# Audio.net
KiCad netlist of a schematic drawn in Altium Designer
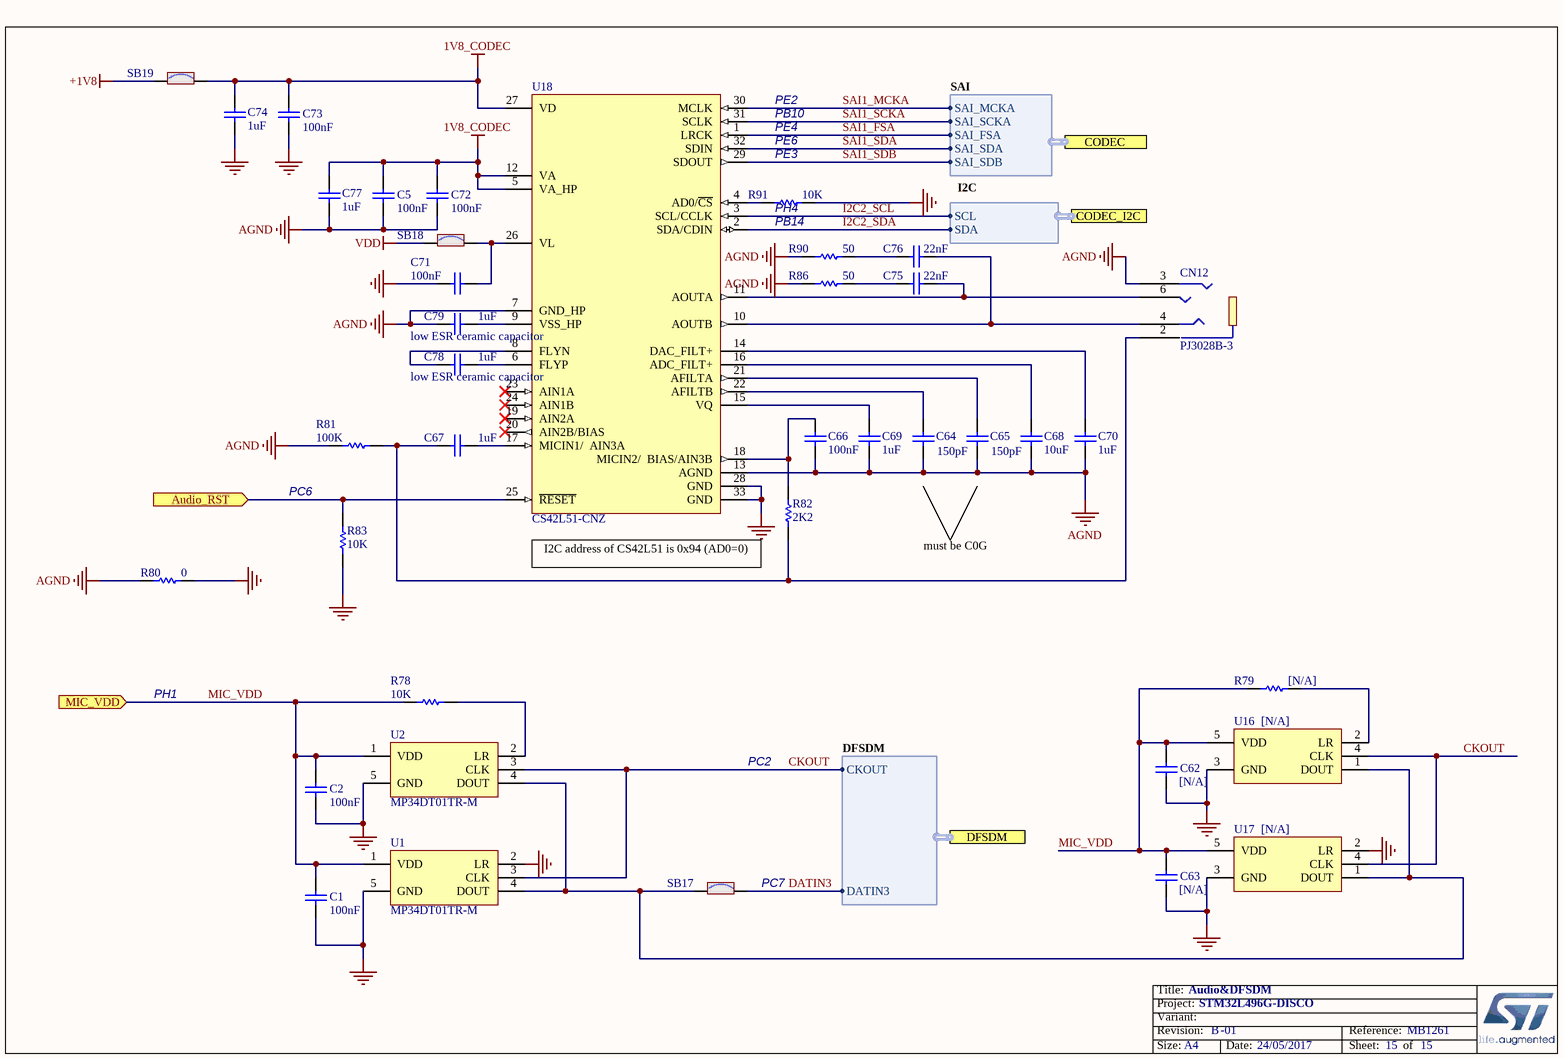
[diagram p0: Audio.SchDoc]

(export (version "E")
  (design (tool "Eeschema 10.0.6"))
  (components
    (comp (ref "C1")
      (value "100nF")
      (footprint "0603C")
      (description "Capacitor,100nF,10%,16V,X7R,0603,YAGEO")
      (fields (field (name "Comment") "CC0603KRX7R7BB104") (field (name "PUBLISHER") "Altium Limited"))
      (libsource (lib "Miscellaneous Devices") (part "Cap"))
    )
    (comp (ref "C2")
      (value "100nF")
      (footprint "0603C")
      (description "Capacitor,100nF,10%,16V,X7R,0603,YAGEO")
      (fields (field (name "Comment") "CC0603KRX7R7BB104") (field (name "PUBLISHER") "Altium Limited"))
      (libsource (lib "Miscellaneous Devices") (part "Cap"))
    )
    (comp (ref "C5")
      (value "100nF")
      (footprint "0603C")
      (description "Capacitor,100nF,10%,16V,X7R,0603,YAGEO")
      (fields (field (name "Comment") "CC0603KRX7R7BB104") (field (name "PUBLISHER") "Altium Limited"))
      (libsource (lib "Miscellaneous Devices") (part "Cap"))
    )
    (comp (ref "C62")
      (value "[N/A]")
      (footprint "0603C")
      (description "Capacitor,100nF,10%,16V,X7R,0603,YAGEO")
      (fields (field (name "PUBLISHER") "Altium Limited"))
      (libsource (lib "Miscellaneous Devices") (part "Cap"))
    )
    (comp (ref "C63")
      (value "[N/A]")
      (footprint "0603C")
      (description "Capacitor,100nF,10%,16V,X7R,0603,YAGEO")
      (fields (field (name "PUBLISHER") "Altium Limited"))
      (libsource (lib "Miscellaneous Devices") (part "Cap"))
    )
    (comp (ref "C64")
      (value "150pF")
      (footprint "0603C")
      (description "Capacitor,150pF,0603,50V,5%,NPO")
      (fields (field (name "Comment") "CC0603JRNPO9BN151") (field (name "PUBLISHER") "Altium Limited"))
      (libsource (lib "Miscellaneous Devices") (part "Cap"))
    )
    (comp (ref "C65")
      (value "150pF")
      (footprint "0603C")
      (description "Capacitor,150pF,0603,50V,5%,NPO")
      (fields (field (name "Comment") "CC0603JRNPO9BN151") (field (name "PUBLISHER") "Altium Limited"))
      (libsource (lib "Miscellaneous Devices") (part "Cap"))
    )
    (comp (ref "C66")
      (value "100nF")
      (footprint "0603C")
      (description "Capacitor,100nF,10%,16V,X7R,0603,YAGEO")
      (fields (field (name "Comment") "CC0603KRX7R7BB104") (field (name "PUBLISHER") "Altium Limited"))
      (libsource (lib "Miscellaneous Devices") (part "Cap"))
    )
    (comp (ref "C67")
      (value "1uF")
      (footprint "0603C")
      (description "Capacitor,1uF,0603,16V,10%,X5R,YAGEO")
      (fields (field (name "Comment") "CC0603KRX5R7BB105") (field (name "PUBLISHER") "Altium Limited"))
      (libsource (lib "Miscellaneous Devices") (part "Cap"))
    )
    (comp (ref "C68")
      (value "10uF")
      (footprint "0603C")
      (description "Capacitor,10uF,10%,10V,X5R,0603,C1608X5R1A106KT000E")
      (fields (field (name "Comment") "C1608X5R1A106KT000E") (field (name "PUBLISHER") "Altium Limited"))
      (libsource (lib "Miscellaneous Devices") (part "Cap"))
    )
    (comp (ref "C69")
      (value "1uF")
      (footprint "0603C")
      (description "Capacitor,1uF,0603,16V,10%,X5R,YAGEO")
      (fields (field (name "Comment") "CC0603KRX5R7BB105") (field (name "PUBLISHER") "Altium Limited"))
      (libsource (lib "Miscellaneous Devices") (part "Cap"))
    )
    (comp (ref "C70")
      (value "1uF")
      (footprint "0603C")
      (description "Capacitor,1uF,0603,16V,10%,X5R,YAGEO")
      (fields (field (name "Comment") "CC0603KRX5R7BB105") (field (name "PUBLISHER") "Altium Limited"))
      (libsource (lib "Miscellaneous Devices") (part "Cap"))
    )
    (comp (ref "C71")
      (value "100nF")
      (footprint "0603C")
      (description "Capacitor,100nF,10%,16V,X7R,0603,YAGEO")
      (fields (field (name "Comment") "CC0603KRX7R7BB104") (field (name "PUBLISHER") "Altium Limited"))
      (libsource (lib "Miscellaneous Devices") (part "Cap"))
    )
    (comp (ref "C72")
      (value "100nF")
      (footprint "0603C")
      (description "Capacitor,100nF,10%,16V,X7R,0603,YAGEO")
      (fields (field (name "Comment") "CC0603KRX7R7BB104") (field (name "PUBLISHER") "Altium Limited"))
      (libsource (lib "Miscellaneous Devices") (part "Cap"))
    )
    (comp (ref "C73")
      (value "100nF")
      (footprint "0603C")
      (description "Capacitor,100nF,10%,16V,X7R,0603,YAGEO")
      (fields (field (name "Comment") "CC0603KRX7R7BB104") (field (name "PUBLISHER") "Altium Limited"))
      (libsource (lib "Miscellaneous Devices") (part "Cap"))
    )
    (comp (ref "C74")
      (value "1uF")
      (footprint "0603C")
      (description "Capacitor,1uF,0603,16V,10%,X5R,YAGEO")
      (fields (field (name "Comment") "CC0603KRX5R7BB105") (field (name "PUBLISHER") "Altium Limited"))
      (libsource (lib "Miscellaneous Devices") (part "Cap"))
    )
    (comp (ref "C75")
      (value "22nF")
      (footprint "0603C")
      (description "Capacitor,22nF,10%,25V,X7R,0603")
      (fields (field (name "Comment") "CC0603KRX7R8BB223") (field (name "PUBLISHER") "Altium Limited"))
      (libsource (lib "Miscellaneous Devices") (part "Cap"))
    )
    (comp (ref "C76")
      (value "22nF")
      (footprint "0603C")
      (description "Capacitor,22nF,10%,25V,X7R,0603")
      (fields (field (name "Comment") "CC0603KRX7R8BB223") (field (name "PUBLISHER") "Altium Limited"))
      (libsource (lib "Miscellaneous Devices") (part "Cap"))
    )
    (comp (ref "C77")
      (value "1uF")
      (footprint "0603C")
      (description "Capacitor,1uF,0603,16V,10%,X5R,YAGEO")
      (fields (field (name "Comment") "CC0603KRX5R7BB105") (field (name "PUBLISHER") "Altium Limited"))
      (libsource (lib "Miscellaneous Devices") (part "Cap"))
    )
    (comp (ref "C78")
      (value "1uF")
      (footprint "0603C")
      (description "Capacitor,1uF,0603,16V,10%,X5R,YAGEO")
      (fields (field (name "Comment") "CC0603KRX5R7BB105") (field (name "PUBLISHER") "Altium Limited"))
      (libsource (lib "Miscellaneous Devices") (part "Cap"))
    )
    (comp (ref "C79")
      (value "1uF")
      (footprint "0603C")
      (description "Capacitor,1uF,0603,16V,10%,X5R,YAGEO")
      (fields (field (name "Comment") "CC0603KRX5R7BB105") (field (name "PUBLISHER") "Altium Limited"))
      (libsource (lib "Miscellaneous Devices") (part "Cap"))
    )
    (comp (ref "CN12") (value "PJ3028B-3") (footprint "PJ3028B") (libsource (lib "MB786") (part "PJ3028B-3")))
    (comp (ref "R78")
      (value "10K")
      (footprint "0603R")
      (description "Resistor,10K,0603,1%,YAGEO")
      (fields (field (name "Comment") "RC0603FR-0710KL") (field (name "PUBLISHER") "Altium Limited"))
      (libsource (lib "Miscellaneous Devices") (part "res1"))
    )
    (comp (ref "R79")
      (value "[N/A]")
      (footprint "0603R")
      (description "Resistor,10K,0603,1%,YAGEO")
      (fields (field (name "PUBLISHER") "Altium Limited"))
      (libsource (lib "Miscellaneous Devices") (part "res1"))
    )
    (comp (ref "R80")
      (value "0")
      (footprint "0603R")
      (description "Resistor, 0 ,0603,1%,YAGEO")
      (fields (field (name "Comment") "RC0603JR-070RL") (field (name "PUBLISHER") "Altium Limited"))
      (libsource (lib "Miscellaneous Devices") (part "res1"))
    )
    (comp (ref "R81")
      (value "100K")
      (footprint "0603R")
      (description "Resistor,100K,0603,1%,YAGEO")
      (fields (field (name "Comment") "RC0603FR-07100KL") (field (name "PUBLISHER") "Altium Limited"))
      (libsource (lib "Miscellaneous Devices") (part "res1"))
    )
    (comp (ref "R82")
      (value "2K2")
      (footprint "0603R")
      (description "Resistor,2.2K,0603,1%,YAGEO")
      (fields (field (name "Comment") "RC0603FR-072K2L") (field (name "PUBLISHER") "Altium Limited"))
      (libsource (lib "Miscellaneous Devices") (part "res1"))
    )
    (comp (ref "R83")
      (value "10K")
      (footprint "0603R")
      (description "Resistor,10K,0603,1%,YAGEO")
      (fields (field (name "Comment") "RC0603FR-0710KL") (field (name "PUBLISHER") "Altium Limited"))
      (libsource (lib "Miscellaneous Devices") (part "res1"))
    )
    (comp (ref "R86")
      (value "50")
      (footprint "0603R")
      (description "Resistor,50R,0603,1%,YAGEO")
      (fields (field (name "Comment") "RC0603FR-0750RL") (field (name "PUBLISHER") "Altium Limited"))
      (libsource (lib "Miscellaneous Devices") (part "res1"))
    )
    (comp (ref "R90")
      (value "50")
      (footprint "0603R")
      (description "Resistor,50R,0603,1%,YAGEO")
      (fields (field (name "Comment") "RC0603FR-0750RL") (field (name "PUBLISHER") "Altium Limited"))
      (libsource (lib "Miscellaneous Devices") (part "res1"))
    )
    (comp (ref "R91")
      (value "10K")
      (footprint "0603R")
      (description "Resistor,10K,0603,1%,YAGEO")
      (fields (field (name "Comment") "RC0603FR-0710KL") (field (name "PUBLISHER") "Altium Limited"))
      (libsource (lib "Miscellaneous Devices") (part "res1"))
    )
    (comp (ref "SB17")
      (value "Solder Bridge ON")
      (footprint "SB_0603")
      (libsource (lib "MCD_TOOLS") (part "SB_ON"))
    )
    (comp (ref "SB18")
      (value "Solder Bridge ON")
      (footprint "SB_0603")
      (libsource (lib "MCD_TOOLS") (part "SB_ON"))
    )
    (comp (ref "SB19")
      (value "Solder Bridge ON")
      (footprint "SB_0603")
      (libsource (lib "MCD_TOOLS") (part "SB_ON"))
    )
    (comp (ref "U1")
      (value "MP34DT01TR-M")
      (footprint "MP34DT01TR")
      (description "MEMS audio sensor")
      (fields (field (name "PUBLISHER") "Altium Limited"))
      (libsource (lib "mb1045") (part "MP34DT01TR"))
    )
    (comp (ref "U2")
      (value "MP34DT01TR-M")
      (footprint "MP34DT01TR")
      (description "MEMS audio sensor")
      (fields (field (name "PUBLISHER") "Altium Limited"))
      (libsource (lib "mb1045") (part "MP34DT01TR"))
    )
    (comp (ref "U16")
      (value "[N/A]")
      (footprint "RHLGA5LD")
      (description "MEMS micro")
      (fields (field (name "PUBLISHER") "STM"))
      (libsource (lib "Big Orga") (part "MP23DB01MM"))
    )
    (comp (ref "U17")
      (value "[N/A]")
      (footprint "RHLGA5LD")
      (description "MEMS micro")
      (fields (field (name "PUBLISHER") "STM"))
      (libsource (lib "Big Orga") (part "MP23DB01MM"))
    )
    (comp (ref "U18")
      (value "CS42L51-CNZ")
      (footprint "QFN32_0R5_5X5")
      (description "Low-Power, Stereo Codec with Headphone Amp")
      (libsource (lib "Big Orga") (part "CS42L51-CNZ"))
    )
  )
  (nets
    (net (code "4") (name "+1V8") (class "Default")
      (node (ref "SB19") (pin "1") (pinfunction "1_1") (pintype "passive"))
    )
    (net (code "5") (name "/Audio_RST") (class "Default")
      (node (ref "R83") (pin "2") (pinfunction "2_2") (pintype "passive"))
      (node (ref "U18") (pin "25") (pinfunction "~{RESET}_25") (pintype "input"))
    )
    (net (code "6") (name "/CKOUT") (class "Default")
      (node (ref "U1") (pin "3") (pinfunction "CLK_3") (pintype "passive"))
      (node (ref "U16") (pin "4") (pinfunction "CLK_4") (pintype "passive"))
      (node (ref "U17") (pin "4") (pinfunction "CLK_4") (pintype "passive"))
      (node (ref "U2") (pin "3") (pinfunction "CLK_3") (pintype "passive"))
    )
    (net (code "7") (name "/DATIN3") (class "Default")
      (node (ref "SB17") (pin "2") (pinfunction "2_2") (pintype "passive"))
    )
    (net (code "8") (name "/I2C2_SCL") (class "Default")
      (node (ref "U18") (pin "3") (pinfunction "SCL/CCLK_3") (pintype "input"))
    )
    (net (code "9") (name "/I2C2_SDA") (class "Default")
      (node (ref "U18") (pin "2") (pinfunction "SDA/CDIN_2") (pintype "bidirectional"))
    )
    (net (code "10") (name "/MIC_VDD") (class "Default")
      (node (ref "C1") (pin "1") (pinfunction "1_1") (pintype "passive"))
      (node (ref "C2") (pin "1") (pinfunction "1_1") (pintype "passive"))
      (node (ref "C62") (pin "1") (pinfunction "1_1") (pintype "passive"))
      (node (ref "C63") (pin "1") (pinfunction "1_1") (pintype "passive"))
      (node (ref "R78") (pin "2") (pinfunction "2_2") (pintype "passive"))
      (node (ref "R79") (pin "2") (pinfunction "2_2") (pintype "passive"))
      (node (ref "U1") (pin "1") (pinfunction "VDD_1") (pintype "passive"))
      (node (ref "U16") (pin "5") (pinfunction "VDD_5") (pintype "passive"))
      (node (ref "U17") (pin "5") (pinfunction "VDD_5") (pintype "passive"))
      (node (ref "U2") (pin "1") (pinfunction "VDD_1") (pintype "passive"))
    )
    (net (code "11") (name "/SAI1_FSA") (class "Default")
      (node (ref "U18") (pin "1") (pinfunction "LRCK_1") (pintype "input"))
    )
    (net (code "12") (name "/SAI1_MCKA") (class "Default")
      (node (ref "U18") (pin "30") (pinfunction "MCLK_30") (pintype "input"))
    )
    (net (code "13") (name "/SAI1_SCKA") (class "Default")
      (node (ref "U18") (pin "31") (pinfunction "SCLK_31") (pintype "input"))
    )
    (net (code "14") (name "/SAI1_SDA") (class "Default")
      (node (ref "U18") (pin "32") (pinfunction "SDIN_32") (pintype "input"))
    )
    (net (code "15") (name "/SAI1_SDB") (class "Default")
      (node (ref "U18") (pin "29") (pinfunction "SDOUT_29") (pintype "output"))
    )
    (net (code "19") (name "1V8_CODEC") (class "Default")
      (node (ref "C5") (pin "1") (pinfunction "1_1") (pintype "passive"))
      (node (ref "C72") (pin "1") (pinfunction "1_1") (pintype "passive"))
      (node (ref "C73") (pin "1") (pinfunction "1_1") (pintype "passive"))
      (node (ref "C74") (pin "1") (pinfunction "1_1") (pintype "passive"))
      (node (ref "C77") (pin "1") (pinfunction "1_1") (pintype "passive"))
      (node (ref "SB19") (pin "2") (pinfunction "2_2") (pintype "passive"))
      (node (ref "U18") (pin "12") (pinfunction "VA_12") (pintype "power_in"))
      (node (ref "U18") (pin "27") (pinfunction "VD_27") (pintype "power_in"))
      (node (ref "U18") (pin "5") (pinfunction "VA_HP_5") (pintype "power_in"))
    )
    (net (code "20") (name "AGND") (class "Default")
      (node (ref "C5") (pin "2") (pinfunction "2_2") (pintype "passive"))
      (node (ref "C64") (pin "2") (pinfunction "2_2") (pintype "passive"))
      (node (ref "C65") (pin "2") (pinfunction "2_2") (pintype "passive"))
      (node (ref "C66") (pin "1") (pinfunction "1_1") (pintype "passive"))
      (node (ref "C68") (pin "1") (pinfunction "1_1") (pintype "passive"))
      (node (ref "C69") (pin "1") (pinfunction "1_1") (pintype "passive"))
      (node (ref "C70") (pin "1") (pinfunction "1_1") (pintype "passive"))
      (node (ref "C72") (pin "2") (pinfunction "2_2") (pintype "passive"))
      (node (ref "C77") (pin "2") (pinfunction "2_2") (pintype "passive"))
      (node (ref "C79") (pin "1") (pinfunction "1_1") (pintype "passive"))
      (node (ref "CN12") (pin "3") (pintype "passive"))
      (node (ref "R80") (pin "2") (pinfunction "2_2") (pintype "passive"))
      (node (ref "R81") (pin "2") (pinfunction "2_2") (pintype "passive"))
      (node (ref "R86") (pin "2") (pinfunction "2_2") (pintype "passive"))
      (node (ref "R90") (pin "2") (pinfunction "2_2") (pintype "passive"))
      (node (ref "U18") (pin "13") (pinfunction "AGND_13") (pintype "power_in"))
      (node (ref "U18") (pin "7") (pinfunction "GND_HP_7") (pintype "power_in"))
    )
    (net (code "21") (name "GND") (class "Default")
      (node (ref "C1") (pin "2") (pinfunction "2_2") (pintype "passive"))
      (node (ref "C2") (pin "2") (pinfunction "2_2") (pintype "passive"))
      (node (ref "C62") (pin "2") (pinfunction "2_2") (pintype "passive"))
      (node (ref "C63") (pin "2") (pinfunction "2_2") (pintype "passive"))
      (node (ref "C71") (pin "1") (pinfunction "1_1") (pintype "passive"))
      (node (ref "C73") (pin "2") (pinfunction "2_2") (pintype "passive"))
      (node (ref "C74") (pin "2") (pinfunction "2_2") (pintype "passive"))
      (node (ref "R80") (pin "1") (pinfunction "1_1") (pintype "passive"))
      (node (ref "R83") (pin "1") (pinfunction "1_1") (pintype "passive"))
      (node (ref "R91") (pin "1") (pinfunction "1_1") (pintype "passive"))
      (node (ref "U1") (pin "2") (pinfunction "LR_2") (pintype "passive"))
      (node (ref "U1") (pin "5") (pinfunction "GND_5") (pintype "passive"))
      (node (ref "U16") (pin "3") (pinfunction "GND_3") (pintype "passive"))
      (node (ref "U17") (pin "2") (pinfunction "LR_2") (pintype "passive"))
      (node (ref "U17") (pin "3") (pinfunction "GND_3") (pintype "passive"))
      (node (ref "U18") (pin "28") (pinfunction "GND_28") (pintype "power_in"))
      (node (ref "U18") (pin "33") (pinfunction "GND_33") (pintype "power_in"))
      (node (ref "U2") (pin "5") (pinfunction "GND_5") (pintype "passive"))
    )
    (net (code "22") (name "Net-(C67-Pad1)") (class "Default")
      (node (ref "C67") (pin "1") (pinfunction "1_1") (pintype "passive"))
      (node (ref "CN12") (pin "2") (pintype "passive"))
      (node (ref "R81") (pin "1") (pinfunction "1_1") (pintype "passive"))
      (node (ref "R82") (pin "1") (pinfunction "1_1") (pintype "passive"))
    )
    (net (code "23") (name "Net-(C75-Pad2)") (class "Default")
      (node (ref "C75") (pin "2") (pinfunction "2_2") (pintype "passive"))
      (node (ref "R86") (pin "1") (pinfunction "1_1") (pintype "passive"))
    )
    (net (code "24") (name "Net-(C76-Pad2)") (class "Default")
      (node (ref "C76") (pin "2") (pinfunction "2_2") (pintype "passive"))
      (node (ref "R90") (pin "1") (pinfunction "1_1") (pintype "passive"))
    )
    (net (code "25") (name "Net-(U1-DOUT)") (class "Default")
      (node (ref "SB17") (pin "1") (pinfunction "1_1") (pintype "passive"))
      (node (ref "U1") (pin "4") (pinfunction "DOUT_4") (pintype "passive"))
      (node (ref "U16") (pin "1") (pinfunction "DOUT_1") (pintype "passive"))
      (node (ref "U17") (pin "1") (pinfunction "DOUT_1") (pintype "passive"))
      (node (ref "U2") (pin "4") (pinfunction "DOUT_4") (pintype "passive"))
    )
    (net (code "26") (name "Net-(U2-LR)") (class "Default")
      (node (ref "R78") (pin "1") (pinfunction "1_1") (pintype "passive"))
      (node (ref "U2") (pin "2") (pinfunction "LR_2") (pintype "passive"))
    )
    (net (code "27") (name "Net-(U16-LR)") (class "Default")
      (node (ref "R79") (pin "1") (pinfunction "1_1") (pintype "passive"))
      (node (ref "U16") (pin "2") (pinfunction "LR_2") (pintype "passive"))
    )
    (net (code "28") (name "Net-(U18-AD0{slash}~{CS})") (class "Default")
      (node (ref "R91") (pin "2") (pinfunction "2_2") (pintype "passive"))
      (node (ref "U18") (pin "4") (pinfunction "AD0/~{CS}_4") (pintype "input"))
    )
    (net (code "29") (name "Net-(U18-ADC_FILT+)") (class "Default")
      (node (ref "C68") (pin "2") (pinfunction "2_2") (pintype "passive"))
      (node (ref "U18") (pin "16") (pinfunction "ADC_FILT+_16") (pintype "power_in"))
    )
    (net (code "30") (name "Net-(U18-AFILTA)") (class "Default")
      (node (ref "C65") (pin "1") (pinfunction "1_1") (pintype "passive"))
      (node (ref "U18") (pin "21") (pinfunction "AFILTA_21") (pintype "output"))
    )
    (net (code "31") (name "Net-(U18-AFILTB)") (class "Default")
      (node (ref "C64") (pin "1") (pinfunction "1_1") (pintype "passive"))
      (node (ref "U18") (pin "22") (pinfunction "AFILTB_22") (pintype "output"))
    )
    (net (code "32") (name "Net-(U18-AOUTA)") (class "Default")
      (node (ref "C75") (pin "1") (pinfunction "1_1") (pintype "passive"))
      (node (ref "CN12") (pin "6") (pintype "passive"))
      (node (ref "U18") (pin "11") (pinfunction "AOUTA_11") (pintype "output"))
    )
    (net (code "33") (name "Net-(U18-AOUTB)") (class "Default")
      (node (ref "C76") (pin "1") (pinfunction "1_1") (pintype "passive"))
      (node (ref "CN12") (pin "4") (pintype "passive"))
      (node (ref "U18") (pin "10") (pinfunction "AOUTB_10") (pintype "output"))
    )
    (net (code "34") (name "Net-(U18-DAC_FILT+)") (class "Default")
      (node (ref "C70") (pin "2") (pinfunction "2_2") (pintype "passive"))
      (node (ref "U18") (pin "14") (pinfunction "DAC_FILT+_14") (pintype "power_in"))
    )
    (net (code "35") (name "Net-(U18-FLYN)") (class "Default")
      (node (ref "C78") (pin "1") (pinfunction "1_1") (pintype "passive"))
      (node (ref "U18") (pin "8") (pinfunction "FLYN_8") (pintype "passive"))
    )
    (net (code "36") (name "Net-(U18-FLYP)") (class "Default")
      (node (ref "C78") (pin "2") (pinfunction "2_2") (pintype "passive"))
      (node (ref "U18") (pin "6") (pinfunction "FLYP_6") (pintype "passive"))
    )
    (net (code "37") (name "Net-(U18-MICIN1{slash}__AIN3A)") (class "Default")
      (node (ref "C67") (pin "2") (pinfunction "2_2") (pintype "passive"))
      (node (ref "U18") (pin "17") (pinfunction "MICIN1/__AIN3A_17") (pintype "input"))
    )
    (net (code "38") (name "Net-(U18-MICIN2{slash}__BIAS{slash}AIN3B)") (class "Default")
      (node (ref "C66") (pin "2") (pinfunction "2_2") (pintype "passive"))
      (node (ref "R82") (pin "2") (pinfunction "2_2") (pintype "passive"))
      (node (ref "U18") (pin "18") (pinfunction "MICIN2/__BIAS/AIN3B_18") (pintype "output"))
    )
    (net (code "39") (name "Net-(U18-VL)") (class "Default")
      (node (ref "C71") (pin "2") (pinfunction "2_2") (pintype "passive"))
      (node (ref "SB18") (pin "2") (pinfunction "2_2") (pintype "passive"))
      (node (ref "U18") (pin "26") (pinfunction "VL_26") (pintype "power_in"))
    )
    (net (code "40") (name "Net-(U18-VQ)") (class "Default")
      (node (ref "C69") (pin "2") (pinfunction "2_2") (pintype "passive"))
      (node (ref "U18") (pin "15") (pinfunction "VQ_15") (pintype "power_in"))
    )
    (net (code "41") (name "Net-(U18-VSS_HP)") (class "Default")
      (node (ref "C79") (pin "2") (pinfunction "2_2") (pintype "passive"))
      (node (ref "U18") (pin "9") (pinfunction "VSS_HP_9") (pintype "power_in"))
    )
    (net (code "42") (name "VDD") (class "Default")
      (node (ref "SB18") (pin "1") (pinfunction "1_1") (pintype "passive"))
    )
    (net (code "43") (name "unconnected-(U18-AIN1A-Pad23)") (class "Default")
      (node (ref "U18") (pin "23") (pinfunction "AIN1A_23") (pintype "input+no_connect"))
    )
    (net (code "44") (name "unconnected-(U18-AIN1B-Pad24)") (class "Default")
      (node (ref "U18") (pin "24") (pinfunction "AIN1B_24") (pintype "input+no_connect"))
    )
    (net (code "45") (name "unconnected-(U18-AIN2A-Pad19)") (class "Default")
      (node (ref "U18") (pin "19") (pinfunction "AIN2A_19") (pintype "input+no_connect"))
    )
    (net (code "46") (name "unconnected-(U18-AIN2B{slash}BIAS-Pad20)") (class "Default")
      (node (ref "U18") (pin "20") (pinfunction "AIN2B/BIAS_20") (pintype "output+no_connect"))
    )
  )
)
